# Industrial_Instrumentation_Controller.net
KiCad netlist of a schematic drawn in Altium Designer
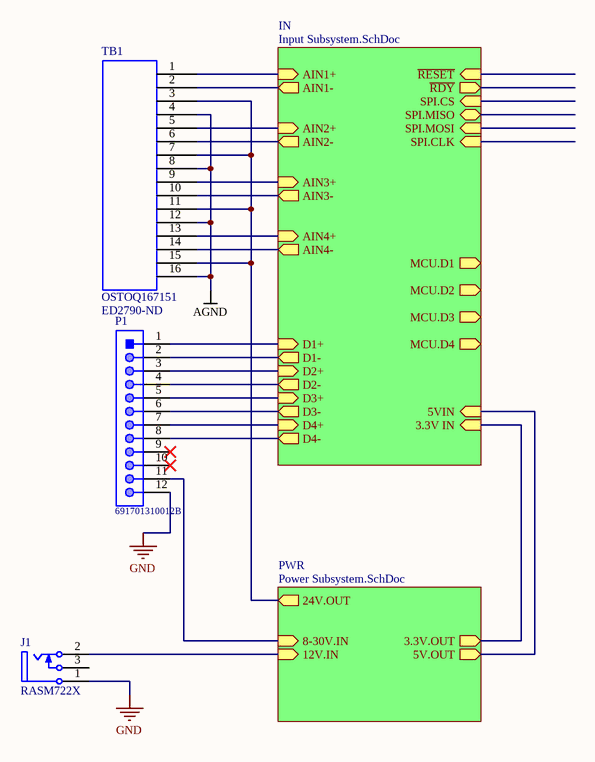
[diagram p0: Industrial Instrumentation Controller.SchDoc]

(export (version "E")
  (design (tool "Eeschema 10.0.6"))
  (components
    (comp (ref "J1")
      (value "RASM722X")
      (footprint "SWIT-RASM722X_V")
      (description "Power Jack, 5 A, 250 V, 3-Pin SMD, RoHS, Bulk")
      (libsource (lib "Altium Content Vault") (part "JACK-2CD3-TN"))
    )
    (comp (ref "P1")
      (value "691701310012B")
      (footprint "691701310012B")
      (description "Serie 7013 B - 3.81mm Vertical PCB Header THR Type WR-TBL, 12 pin")
      (fields (field (name "MANUFACTURER") "Wurth Elektronik") (field (name "PUBLISHER") "WurthElektronik"))
      (libsource (lib "Altium Content Vault") (part "WE-CN-1P-M-R12"))
    )
    (comp (ref "TB1")
      (value "OSTOQ167151")
      (footprint "OSTOQ167151")
      (fields (field (name "SUPPLIER PART NUMBER 1") "ED2790-ND"))
      (libsource (lib "Parts") (part "OSTOQ167151"))
    )
  )
  (nets
    (net (code "3") (name "/8-30V.IN") (class "Default")
      (node (ref "P1") (pin "11") (pinfunction "11_11") (pintype "passive"))
    )
    (net (code "4") (name "/12V.IN") (class "Default")
      (node (ref "J1") (pin "2") (pinfunction "TIP_2") (pintype "passive"))
    )
    (net (code "5") (name "/24V.OUT") (class "Default")
      (node (ref "TB1") (pin "11") (pinfunction "11_11") (pintype "passive"))
      (node (ref "TB1") (pin "15") (pinfunction "15_15") (pintype "passive"))
      (node (ref "TB1") (pin "3") (pinfunction "3_3") (pintype "passive"))
      (node (ref "TB1") (pin "7") (pinfunction "7_7") (pintype "passive"))
    )
    (net (code "6") (name "/AIN1+") (class "Default")
      (node (ref "TB1") (pin "1") (pinfunction "1_1") (pintype "passive"))
    )
    (net (code "7") (name "/AIN1-") (class "Default")
      (node (ref "TB1") (pin "2") (pinfunction "2_2") (pintype "passive"))
    )
    (net (code "8") (name "/AIN2+") (class "Default")
      (node (ref "TB1") (pin "5") (pinfunction "5_5") (pintype "passive"))
    )
    (net (code "9") (name "/AIN2-") (class "Default")
      (node (ref "TB1") (pin "6") (pinfunction "6_6") (pintype "passive"))
    )
    (net (code "10") (name "/AIN3+") (class "Default")
      (node (ref "TB1") (pin "9") (pinfunction "9_9") (pintype "passive"))
    )
    (net (code "11") (name "/AIN3-") (class "Default")
      (node (ref "TB1") (pin "10") (pinfunction "10_10") (pintype "passive"))
    )
    (net (code "12") (name "/AIN4+") (class "Default")
      (node (ref "TB1") (pin "13") (pinfunction "13_13") (pintype "passive"))
    )
    (net (code "13") (name "/AIN4-") (class "Default")
      (node (ref "TB1") (pin "14") (pinfunction "14_14") (pintype "passive"))
    )
    (net (code "14") (name "/D1+") (class "Default")
      (node (ref "P1") (pin "1") (pinfunction "1_1") (pintype "passive"))
    )
    (net (code "15") (name "/D1-") (class "Default")
      (node (ref "P1") (pin "2") (pinfunction "2_2") (pintype "passive"))
    )
    (net (code "16") (name "/D2+") (class "Default")
      (node (ref "P1") (pin "3") (pinfunction "3_3") (pintype "passive"))
    )
    (net (code "17") (name "/D2-") (class "Default")
      (node (ref "P1") (pin "4") (pinfunction "4_4") (pintype "passive"))
    )
    (net (code "18") (name "/D3+") (class "Default")
      (node (ref "P1") (pin "5") (pinfunction "5_5") (pintype "passive"))
    )
    (net (code "19") (name "/D3-") (class "Default")
      (node (ref "P1") (pin "6") (pinfunction "6_6") (pintype "passive"))
    )
    (net (code "20") (name "/D4+") (class "Default")
      (node (ref "P1") (pin "7") (pinfunction "7_7") (pintype "passive"))
    )
    (net (code "21") (name "/D4-") (class "Default")
      (node (ref "P1") (pin "8") (pinfunction "8_8") (pintype "passive"))
    )
    (net (code "32") (name "AGND") (class "Default")
      (node (ref "TB1") (pin "12") (pinfunction "12_12") (pintype "passive"))
      (node (ref "TB1") (pin "16") (pinfunction "16_16") (pintype "passive"))
      (node (ref "TB1") (pin "4") (pinfunction "4_4") (pintype "passive"))
      (node (ref "TB1") (pin "8") (pinfunction "8_8") (pintype "passive"))
    )
    (net (code "33") (name "GND") (class "Default")
      (node (ref "J1") (pin "1") (pinfunction "SLEEVE_1") (pintype "passive"))
      (node (ref "P1") (pin "12") (pinfunction "12_12") (pintype "passive"))
    )
    (net (code "34") (name "unconnected-(J1-SHUNT-Pad3)") (class "Default")
      (node (ref "J1") (pin "3") (pinfunction "SHUNT_3") (pintype "passive"))
    )
    (net (code "35") (name "unconnected-(P1-Pad9)") (class "Default")
      (node (ref "P1") (pin "9") (pinfunction "9_9") (pintype "passive+no_connect"))
    )
    (net (code "36") (name "unconnected-(P1-Pad10)") (class "Default")
      (node (ref "P1") (pin "10") (pinfunction "10_10") (pintype "passive+no_connect"))
    )
  )
)
